# Sheet1.net
KiCad netlist of a schematic drawn in Altium Designer
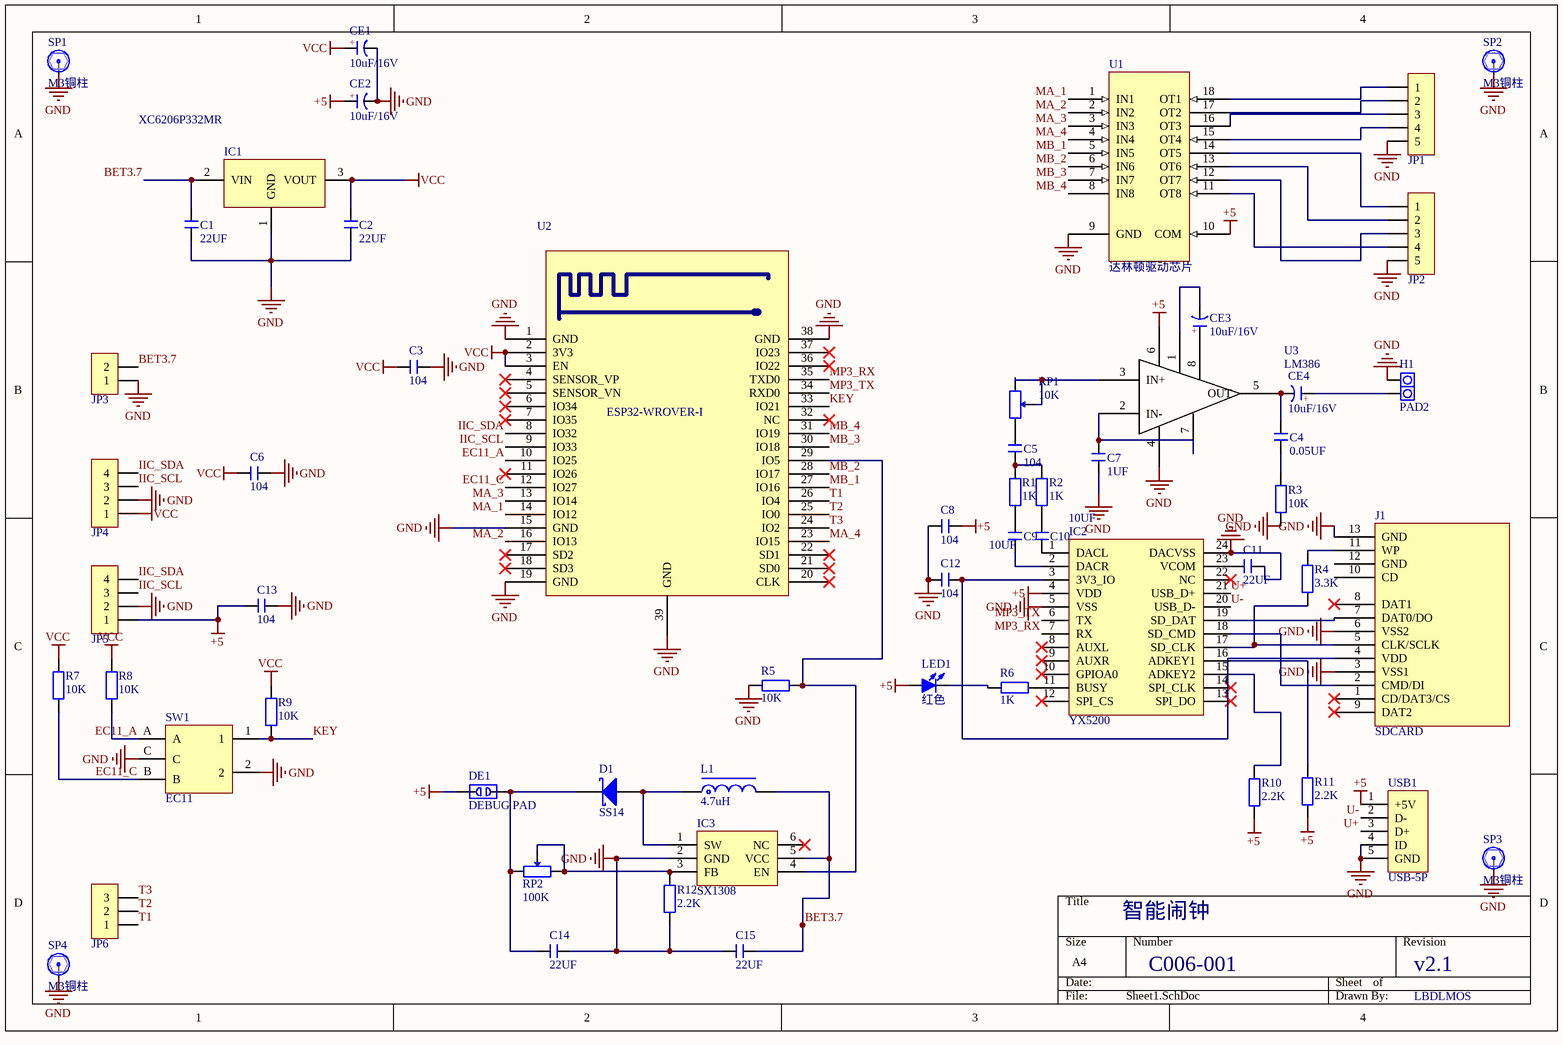
[diagram p0: Sheet1.SchDoc]

(export (version "E")
  (design (tool "Eeschema 10.0.6"))
  (components
    (comp (ref "C1")
      (value "22UF")
      (footprint "C 0603_L")
      (description "贴片电容")
      (libsource (lib "0.1 - 电阻-电容-电感") (part "C"))
    )
    (comp (ref "C2")
      (value "22UF")
      (footprint "C 0603_L")
      (description "贴片电容")
      (libsource (lib "0.1 - 电阻-电容-电感") (part "C"))
    )
    (comp (ref "C3")
      (value "104")
      (footprint "C 0805_L")
      (description "贴片电容")
      (libsource (lib "0.1 - 电阻-电容-电感") (part "C"))
    )
    (comp (ref "C4")
      (value "0.05UF")
      (footprint "C 0603_L")
      (description "贴片电容")
      (libsource (lib "0.1 - 电阻-电容-电感") (part "C"))
    )
    (comp (ref "C5")
      (value "104")
      (footprint "C 0805_L")
      (description "贴片电容")
      (libsource (lib "0.1 - 电阻-电容-电感") (part "C"))
    )
    (comp (ref "C6")
      (value "104")
      (footprint "C 0805_L")
      (description "贴片电容")
      (libsource (lib "0.1 - 电阻-电容-电感") (part "C"))
    )
    (comp (ref "C7")
      (value "1UF")
      (footprint "C 0603_L")
      (description "贴片电容")
      (libsource (lib "0.1 - 电阻-电容-电感") (part "C"))
    )
    (comp (ref "C8")
      (value "104")
      (footprint "C 0603_L")
      (description "贴片电容")
      (libsource (lib "0.1 - 电阻-电容-电感") (part "C"))
    )
    (comp (ref "C9")
      (value "10UF")
      (footprint "C 0603_L")
      (description "贴片电容")
      (libsource (lib "0.1 - 电阻-电容-电感") (part "C"))
    )
    (comp (ref "C10")
      (value "10UF")
      (footprint "C 0603_L")
      (description "贴片电容")
      (libsource (lib "0.1 - 电阻-电容-电感") (part "C"))
    )
    (comp (ref "C11")
      (value "22UF")
      (footprint "C 0805_L")
      (description "贴片电容")
      (libsource (lib "0.1 - 电阻-电容-电感") (part "C"))
    )
    (comp (ref "C12")
      (value "104")
      (footprint "C 0603_L")
      (description "贴片电容")
      (libsource (lib "0.1 - 电阻-电容-电感") (part "C"))
    )
    (comp (ref "C13")
      (value "104")
      (footprint "C 0805_L")
      (description "贴片电容")
      (libsource (lib "0.1 - 电阻-电容-电感") (part "C"))
    )
    (comp (ref "C14")
      (value "22UF")
      (footprint "C 0603_L")
      (description "贴片电容")
      (libsource (lib "0.1 - 电阻-电容-电感") (part "C"))
    )
    (comp (ref "C15")
      (value "22UF")
      (footprint "C 0603_L")
      (description "贴片电容")
      (libsource (lib "0.1 - 电阻-电容-电感") (part "C"))
    )
    (comp (ref "CE1")
      (value "10uF/16V")
      (footprint "CAP 1.5*4*8")
      (description "直插电解电容")
      (libsource (lib "0.1 - 电阻-电容-电感") (part "CE"))
    )
    (comp (ref "CE2")
      (value "10uF/16V")
      (footprint "CAP 1.5*4*8")
      (description "直插电解电容")
      (libsource (lib "0.1 - 电阻-电容-电感") (part "CE"))
    )
    (comp (ref "CE3")
      (value "10uF/16V")
      (footprint "CAP 1.5*4*8")
      (description "直插电解电容")
      (libsource (lib "") (part "CE_1"))
    )
    (comp (ref "CE4")
      (value "10uF/16V")
      (footprint "CAP 1.5*4*8")
      (description "直插电解电容")
      (libsource (lib "0.1 - 电阻-电容-电感") (part "CE"))
    )
    (comp (ref "D1")
      (value "SS14")
      (footprint "SMA")
      (description "肖特基二极管")
      (libsource (lib "0.2 -  二极管-整流桥") (part "SS14"))
    )
    (comp (ref "DE1")
      (value "DEBUG PAD")
      (footprint "DEBUG_A")
      (description "调试断点焊盘")
      (fields (field (name "版权归属") "封装库来自淘宝 ID：黄晶宝石"))
      (libsource (lib "4.1 - 未分类器件") (part "DEBUG"))
    )
    (comp (ref "H1")
      (value "PAD2")
      (footprint "PAD2-5.08")
      (description "引线焊盘")
      (fields (field (name "版权归属") "封装库来自淘宝 ID：黄晶宝石"))
      (libsource (lib "4.1 - 未分类器件") (part "PAD2"))
    )
    (comp (ref "IC1")
      (value "XC6206P332MR")
      (footprint "SOT-23")
      (libsource (lib "1.1 - 电源类芯片") (part "XC6206P332MR"))
    )
    (comp (ref "IC2")
      (value "YX5200")
      (footprint "SSOP24_N")
      (description "MP3解码芯片")
      (fields (field (name "版权归属") "封装库来自淘宝 ID：黄晶宝石"))
      (libsource (lib "1.0 - 常见芯片") (part "YX5200"))
    )
    (comp (ref "IC3")
      (value "SX1308")
      (footprint "SOT23-6N")
      (description "可调升压芯片")
      (fields (field (name "版权归属") "封装库来自淘宝 ID：黄晶宝石"))
      (libsource (lib "1.1 - 电源类芯片") (part "SX1308"))
    )
    (comp (ref "J1")
      (value "SDCARD")
      (footprint "SDCARD_B")
      (description "SD卡自弹")
      (libsource (lib "1.0 - 常见芯片") (part "SDCARD"))
    )
    (comp (ref "JP1")
      (value "HDR-1X5")
      (footprint "HDR2.54-LI-5P")
      (description "5P接插件")
      (fields (field (name "版权归属") "封装库来自淘宝 ID：黄晶宝石"))
      (libsource (lib "5.3 - 接插件-脚距2.54 (100mil) ") (part "Header 5"))
    )
    (comp (ref "JP2")
      (value "HDR-1X5")
      (footprint "HDR2.54-LI-5P")
      (description "5P接插件")
      (fields (field (name "版权归属") "封装库来自淘宝 ID：黄晶宝石"))
      (libsource (lib "5.3 - 接插件-脚距2.54 (100mil) ") (part "Header 5"))
    )
    (comp (ref "JP3")
      (value "HDR-1X2")
      (footprint "HDR2.54-LI-2P")
      (description "2P接插件")
      (fields (field (name "版权归属") "封装库来自淘宝 ID：黄晶宝石"))
      (libsource (lib "5.3 - 接插件-脚距2.54 (100mil) ") (part "Header 2"))
    )
    (comp (ref "JP4")
      (value "HDR-1X4")
      (footprint "XH2.54-WI-4P")
      (description "4P接插件")
      (fields (field (name "版权归属") "封装库来自淘宝 ID：黄晶宝石"))
      (libsource (lib "5.3 - 接插件-脚距2.54 (100mil) ") (part "Header 4"))
    )
    (comp (ref "JP5")
      (value "HDR-1X4")
      (footprint "XH2.54-WI-4P")
      (description "4P接插件")
      (fields (field (name "版权归属") "封装库来自淘宝 ID：黄晶宝石"))
      (libsource (lib "5.3 - 接插件-脚距2.54 (100mil) ") (part "Header 4"))
    )
    (comp (ref "JP6")
      (value "HDR-1X3")
      (footprint "XH2.54-WI-3P")
      (description "3P接插件")
      (fields (field (name "版权归属") "封装库来自淘宝 ID：黄晶宝石"))
      (libsource (lib "5.3 - 接插件-脚距2.54 (100mil) ") (part "Header 3"))
    )
    (comp (ref "L1")
      (value "4.7uH")
      (footprint "CDRH73")
      (description "功率屏蔽电感")
      (fields (field (name "版权归属") "封装库来自淘宝 ID：黄晶宝石"))
      (libsource (lib "0.1 - 电阻-电容-电感") (part "L-CDRH"))
    )
    (comp (ref "LED1")
      (value "红色")
      (footprint "LED 0603B")
      (description "贴片LED")
      (fields (field (name "版权归属") "封装库来自淘宝 ID：黄晶宝石"))
      (libsource (lib "0.3 - LED发光二极管") (part "LED-SMD"))
    )
    (comp (ref "R1")
      (value "1K")
      (footprint "R 0603_L")
      (description "贴片电阻")
      (fields (field (name "版权归属") "来自淘宝 ID：黄晶宝石"))
      (libsource (lib "0.1 - 电阻-电容-电感") (part "R"))
    )
    (comp (ref "R2")
      (value "1K")
      (footprint "R 0603_L")
      (description "贴片电阻")
      (fields (field (name "版权归属") "来自淘宝 ID：黄晶宝石"))
      (libsource (lib "0.1 - 电阻-电容-电感") (part "R"))
    )
    (comp (ref "R3")
      (value "10K")
      (footprint "R 0603_L")
      (description "贴片电阻")
      (fields (field (name "版权归属") "来自淘宝 ID：黄晶宝石"))
      (libsource (lib "0.1 - 电阻-电容-电感") (part "R"))
    )
    (comp (ref "R4")
      (value "3.3K")
      (footprint "R 0603_L")
      (description "贴片电阻")
      (fields (field (name "版权归属") "来自淘宝 ID：黄晶宝石"))
      (libsource (lib "0.1 - 电阻-电容-电感") (part "R"))
    )
    (comp (ref "R5")
      (value "10K")
      (footprint "R 0805_L")
      (description "贴片电阻")
      (fields (field (name "版权归属") "来自淘宝 ID：黄晶宝石"))
      (libsource (lib "0.1 - 电阻-电容-电感") (part "R"))
    )
    (comp (ref "R6")
      (value "1K")
      (footprint "R 0603_L")
      (description "贴片电阻")
      (fields (field (name "版权归属") "来自淘宝 ID：黄晶宝石"))
      (libsource (lib "0.1 - 电阻-电容-电感") (part "R"))
    )
    (comp (ref "R7")
      (value "10K")
      (footprint "R 0603_L")
      (description "贴片电阻")
      (fields (field (name "版权归属") "来自淘宝 ID：黄晶宝石"))
      (libsource (lib "0.1 - 电阻-电容-电感") (part "R"))
    )
    (comp (ref "R8")
      (value "10K")
      (footprint "R 0603_L")
      (description "贴片电阻")
      (fields (field (name "版权归属") "来自淘宝 ID：黄晶宝石"))
      (libsource (lib "0.1 - 电阻-电容-电感") (part "R"))
    )
    (comp (ref "R9")
      (value "10K")
      (footprint "R 0603_L")
      (description "贴片电阻")
      (fields (field (name "版权归属") "来自淘宝 ID：黄晶宝石"))
      (libsource (lib "0.1 - 电阻-电容-电感") (part "R"))
    )
    (comp (ref "R10")
      (value "2.2K")
      (footprint "R 0603_L")
      (description "贴片电阻")
      (fields (field (name "版权归属") "来自淘宝 ID：黄晶宝石"))
      (libsource (lib "0.1 - 电阻-电容-电感") (part "R"))
    )
    (comp (ref "R11")
      (value "2.2K")
      (footprint "R 0603_L")
      (description "贴片电阻")
      (fields (field (name "版权归属") "来自淘宝 ID：黄晶宝石"))
      (libsource (lib "0.1 - 电阻-电容-电感") (part "R"))
    )
    (comp (ref "R12")
      (value "2.2K")
      (footprint "R 0603_L")
      (description "贴片电阻")
      (fields (field (name "版权归属") "来自淘宝 ID：黄晶宝石"))
      (libsource (lib "0.1 - 电阻-电容-电感") (part "R"))
    )
    (comp (ref "RP1")
      (value "10K")
      (footprint "3296W")
      (description "单联电位器")
      (fields (field (name "版权归属") "封装库来自淘宝 ID：黄晶宝石"))
      (libsource (lib "0.1 - 电阻-电容-电感") (part "RP"))
    )
    (comp (ref "RP2")
      (value "100K")
      (footprint "3296W")
      (description "单联电位器")
      (fields (field (name "版权归属") "封装库来自淘宝 ID：黄晶宝石"))
      (libsource (lib "0.1 - 电阻-电容-电感") (part "RP"))
    )
    (comp (ref "SP1")
      (value "M3铜柱")
      (footprint "M3x4+6_L")
      (description "铜柱")
      (fields (field (name "版权归属") "封装库来自淘宝 ID：黄晶宝石"))
      (libsource (lib "4.1 - 未分类器件") (part "铜柱加头小焊盘"))
    )
    (comp (ref "SP2")
      (value "M3铜柱")
      (footprint "M3x4+6_L")
      (description "铜柱")
      (fields (field (name "版权归属") "封装库来自淘宝 ID：黄晶宝石"))
      (libsource (lib "4.1 - 未分类器件") (part "铜柱加头小焊盘"))
    )
    (comp (ref "SP3")
      (value "M3铜柱")
      (footprint "M3x4+6_L")
      (description "铜柱")
      (fields (field (name "版权归属") "封装库来自淘宝 ID：黄晶宝石"))
      (libsource (lib "4.1 - 未分类器件") (part "铜柱加头小焊盘"))
    )
    (comp (ref "SP4")
      (value "M3铜柱")
      (footprint "M3x4+6_L")
      (description "铜柱")
      (fields (field (name "版权归属") "封装库来自淘宝 ID：黄晶宝石"))
      (libsource (lib "4.1 - 未分类器件") (part "铜柱加头小焊盘"))
    )
    (comp (ref "SW1")
      (value "EC11")
      (footprint "EC11-B")
      (description "数字开关编码器")
      (fields (field (name "版权归属") "封装库来自淘宝 ID：黄晶宝石"))
      (libsource (lib "0.7 - 常用按键-开关") (part "EC11"))
    )
    (comp (ref "U1")
      (value "达林顿驱动芯片")
      (footprint "DIP18-300")
      (libsource (lib "1.0 - 常见芯片") (part "ULN2803"))
    )
    (comp (ref "U2")
      (value "ESP32-WROVER-I")
      (footprint "ESP32-WROVER-I")
      (libsource (lib "0.9 - 电路模块") (part "ESP32-WROVER-I"))
    )
    (comp (ref "U3")
      (value "LM386")
      (footprint "DIP-8")
      (description "音频放大器")
      (libsource (lib "1.0 - 常见芯片") (part "LM386"))
    )
    (comp (ref "USB1")
      (value "USB-5P")
      (footprint "USB-MICRO_A")
      (description "微型USB母座")
      (libsource (lib "0.8 - 以太网-音频-USB插座") (part "USB-5P"))
    )
  )
  (nets
    (net (code "1") (name "+5") (class "Default")
      (node (ref "C13") (pin "1") (pinfunction "1_1") (pintype "passive"))
      (node (ref "C8") (pin "2") (pinfunction "2_2") (pintype "passive"))
      (node (ref "CE2") (pin "1") (pinfunction "A_1") (pintype "passive"))
      (node (ref "DE1") (pin "1") (pinfunction "1_1") (pintype "passive"))
      (node (ref "IC2") (pin "4") (pinfunction "VDD_4") (pintype "passive"))
      (node (ref "JP5") (pin "1") (pinfunction "1_1") (pintype "passive"))
      (node (ref "LED1") (pin "1") (pinfunction "A_1") (pintype "passive"))
      (node (ref "R10") (pin "1") (pinfunction "1_1") (pintype "passive"))
      (node (ref "R11") (pin "1") (pinfunction "1_1") (pintype "passive"))
      (node (ref "U1") (pin "10") (pinfunction "COM_10") (pintype "input"))
      (node (ref "U3") (pin "6") (pintype "passive"))
      (node (ref "USB1") (pin "1") (pinfunction "+5V_1") (pintype "passive"))
    )
    (net (code "2") (name "/BET3.7") (class "Default")
      (node (ref "C1") (pin "2") (pinfunction "2_2") (pintype "passive"))
      (node (ref "C15") (pin "2") (pinfunction "2_2") (pintype "passive"))
      (node (ref "IC1") (pin "2") (pinfunction "VIN_2") (pintype "passive"))
      (node (ref "IC3") (pin "5") (pinfunction "VCC_5") (pintype "passive"))
      (node (ref "JP3") (pin "2") (pinfunction "2_2") (pintype "passive"))
      (node (ref "L1") (pin "2") (pinfunction "2_2") (pintype "passive"))
    )
    (net (code "3") (name "/EC11_A") (class "Default")
      (node (ref "R8") (pin "1") (pinfunction "1_1") (pintype "passive"))
      (node (ref "SW1") (pin "A") (pinfunction "A_A") (pintype "passive"))
      (node (ref "U2") (pin "10") (pinfunction "IO25_10") (pintype "passive"))
    )
    (net (code "4") (name "/EC11_C") (class "Default")
      (node (ref "R7") (pin "1") (pinfunction "1_1") (pintype "passive"))
      (node (ref "SW1") (pin "B") (pinfunction "B_B") (pintype "passive"))
      (node (ref "U2") (pin "12") (pinfunction "IO27_12") (pintype "passive"))
    )
    (net (code "5") (name "/IIC_SCL") (class "Default")
      (node (ref "JP4") (pin "3") (pinfunction "3_3") (pintype "passive"))
      (node (ref "JP5") (pin "3") (pinfunction "3_3") (pintype "passive"))
      (node (ref "U2") (pin "9") (pinfunction "IO33_9") (pintype "passive"))
    )
    (net (code "6") (name "/IIC_SDA") (class "Default")
      (node (ref "JP4") (pin "4") (pinfunction "4_4") (pintype "passive"))
      (node (ref "JP5") (pin "4") (pinfunction "4_4") (pintype "passive"))
      (node (ref "U2") (pin "8") (pinfunction "IO32_8") (pintype "passive"))
    )
    (net (code "7") (name "/KEY") (class "Default")
      (node (ref "R9") (pin "1") (pinfunction "1_1") (pintype "passive"))
      (node (ref "SW1") (pin "1") (pinfunction "1_1") (pintype "passive"))
      (node (ref "U2") (pin "33") (pinfunction "IO21_33") (pintype "passive"))
    )
    (net (code "8") (name "/MA_1") (class "Default")
      (node (ref "U1") (pin "1") (pinfunction "IN1_1") (pintype "input"))
      (node (ref "U2") (pin "14") (pinfunction "IO12_14") (pintype "passive"))
    )
    (net (code "9") (name "/MA_2") (class "Default")
      (node (ref "U1") (pin "2") (pinfunction "IN2_2") (pintype "input"))
      (node (ref "U2") (pin "16") (pinfunction "IO13_16") (pintype "passive"))
    )
    (net (code "10") (name "/MA_3") (class "Default")
      (node (ref "U1") (pin "3") (pinfunction "IN3_3") (pintype "input"))
      (node (ref "U2") (pin "13") (pinfunction "IO14_13") (pintype "passive"))
    )
    (net (code "11") (name "/MA_4") (class "Default")
      (node (ref "U1") (pin "4") (pinfunction "IN4_4") (pintype "input"))
      (node (ref "U2") (pin "23") (pinfunction "IO15_23") (pintype "passive"))
    )
    (net (code "12") (name "/MB_1") (class "Default")
      (node (ref "U1") (pin "5") (pinfunction "IN5_5") (pintype "input"))
      (node (ref "U2") (pin "27") (pinfunction "IO16_27") (pintype "passive"))
    )
    (net (code "13") (name "/MB_2") (class "Default")
      (node (ref "U1") (pin "6") (pinfunction "IN6_6") (pintype "input"))
      (node (ref "U2") (pin "28") (pinfunction "IO17_28") (pintype "passive"))
    )
    (net (code "14") (name "/MB_3") (class "Default")
      (node (ref "U1") (pin "7") (pinfunction "IN7_7") (pintype "input"))
      (node (ref "U2") (pin "30") (pinfunction "IO18_30") (pintype "passive"))
    )
    (net (code "15") (name "/MB_4") (class "Default")
      (node (ref "U1") (pin "8") (pinfunction "IN8_8") (pintype "passive"))
      (node (ref "U2") (pin "31") (pinfunction "IO19_31") (pintype "passive"))
    )
    (net (code "16") (name "/MP3_RX") (class "Default")
      (node (ref "IC2") (pin "7") (pinfunction "RX_7") (pintype "passive"))
      (node (ref "U2") (pin "35") (pinfunction "TXD0_35") (pintype "passive"))
    )
    (net (code "17") (name "/MP3_TX") (class "Default")
      (node (ref "IC2") (pin "6") (pinfunction "TX_6") (pintype "passive"))
      (node (ref "U2") (pin "34") (pinfunction "RXD0_34") (pintype "passive"))
    )
    (net (code "18") (name "/T1") (class "Default")
      (node (ref "JP6") (pin "1") (pinfunction "1_1") (pintype "passive"))
      (node (ref "U2") (pin "26") (pinfunction "IO4_26") (pintype "passive"))
    )
    (net (code "19") (name "/T2") (class "Default")
      (node (ref "JP6") (pin "2") (pinfunction "2_2") (pintype "passive"))
      (node (ref "U2") (pin "25") (pinfunction "IO0_25") (pintype "passive"))
    )
    (net (code "20") (name "/T3") (class "Default")
      (node (ref "JP6") (pin "3") (pinfunction "3_3") (pintype "passive"))
      (node (ref "U2") (pin "24") (pinfunction "IO2_24") (pintype "passive"))
    )
    (net (code "21") (name "/U+") (class "Default")
      (node (ref "IC2") (pin "21") (pinfunction "USB_D+_21") (pintype "passive"))
      (node (ref "USB1") (pin "3") (pinfunction "D+_3") (pintype "passive"))
    )
    (net (code "22") (name "/U-") (class "Default")
      (node (ref "IC2") (pin "20") (pinfunction "USB_D-_20") (pintype "passive"))
      (node (ref "USB1") (pin "2") (pinfunction "D-_2") (pintype "passive"))
    )
    (net (code "23") (name "GND") (class "Default")
      (node (ref "C1") (pin "1") (pinfunction "1_1") (pintype "passive"))
      (node (ref "C11") (pin "2") (pinfunction "2_2") (pintype "passive"))
      (node (ref "C12") (pin "1") (pinfunction "1_1") (pintype "passive"))
      (node (ref "C13") (pin "2") (pinfunction "2_2") (pintype "passive"))
      (node (ref "C14") (pin "2") (pinfunction "2_2") (pintype "passive"))
      (node (ref "C15") (pin "1") (pinfunction "1_1") (pintype "passive"))
      (node (ref "C2") (pin "1") (pinfunction "1_1") (pintype "passive"))
      (node (ref "C3") (pin "2") (pinfunction "2_2") (pintype "passive"))
      (node (ref "C6") (pin "2") (pinfunction "2_2") (pintype "passive"))
      (node (ref "C7") (pin "1") (pinfunction "1_1") (pintype "passive"))
      (node (ref "C8") (pin "1") (pinfunction "1_1") (pintype "passive"))
      (node (ref "CE1") (pin "2") (pinfunction "K_2") (pintype "passive"))
      (node (ref "CE2") (pin "2") (pinfunction "K_2") (pintype "passive"))
      (node (ref "H1") (pin "1") (pinfunction "1_1") (pintype "passive"))
      (node (ref "IC1") (pin "1") (pinfunction "GND_1") (pintype "passive"))
      (node (ref "IC2") (pin "24") (pinfunction "DACVSS_24") (pintype "passive"))
      (node (ref "IC2") (pin "5") (pinfunction "VSS_5") (pintype "passive"))
      (node (ref "IC3") (pin "2") (pinfunction "GND_2") (pintype "passive"))
      (node (ref "J1") (pin "13") (pinfunction "GND_13") (pintype "passive"))
      (node (ref "J1") (pin "3") (pinfunction "VSS1_3") (pintype "passive"))
      (node (ref "J1") (pin "6") (pinfunction "VSS2_6") (pintype "passive"))
      (node (ref "JP1") (pin "5") (pinfunction "5_5") (pintype "passive"))
      (node (ref "JP2") (pin "5") (pinfunction "5_5") (pintype "passive"))
      (node (ref "JP3") (pin "1") (pinfunction "1_1") (pintype "passive"))
      (node (ref "JP4") (pin "2") (pinfunction "2_2") (pintype "passive"))
      (node (ref "JP5") (pin "2") (pinfunction "2_2") (pintype "passive"))
      (node (ref "R12") (pin "1") (pinfunction "1_1") (pintype "passive"))
      (node (ref "R3") (pin "1") (pinfunction "1_1") (pintype "passive"))
      (node (ref "R5") (pin "1") (pinfunction "1_1") (pintype "passive"))
      (node (ref "SP1") (pin "1") (pinfunction "1_1") (pintype "passive"))
      (node (ref "SP2") (pin "1") (pinfunction "1_1") (pintype "passive"))
      (node (ref "SP3") (pin "1") (pinfunction "1_1") (pintype "passive"))
      (node (ref "SP4") (pin "1") (pinfunction "1_1") (pintype "passive"))
      (node (ref "SW1") (pin "2") (pinfunction "2_2") (pintype "passive"))
      (node (ref "SW1") (pin "C") (pinfunction "C_C") (pintype "passive"))
      (node (ref "U1") (pin "9") (pinfunction "GND_9") (pintype "power_in"))
      (node (ref "U2") (pin "1") (pinfunction "GND_1") (pintype "passive"))
      (node (ref "U2") (pin "15") (pinfunction "GND_15") (pintype "passive"))
      (node (ref "U2") (pin "19") (pinfunction "GND_19") (pintype "passive"))
      (node (ref "U2") (pin "38") (pinfunction "GND_38") (pintype "passive"))
      (node (ref "U2") (pin "39") (pinfunction "GND_39") (pintype "passive"))
      (node (ref "U3") (pin "4") (pintype "passive"))
      (node (ref "USB1") (pin "4") (pinfunction "ID_4") (pintype "passive"))
      (node (ref "USB1") (pin "5") (pinfunction "GND_5") (pintype "passive"))
    )
    (net (code "24") (name "Net-(C4-Pad1)") (class "Default")
      (node (ref "C4") (pin "1") (pinfunction "1_1") (pintype "passive"))
      (node (ref "R3") (pin "2") (pinfunction "2_2") (pintype "passive"))
    )
    (net (code "25") (name "Net-(C5-Pad1)") (class "Default")
      (node (ref "C5") (pin "1") (pinfunction "1_1") (pintype "passive"))
      (node (ref "R1") (pin "2") (pinfunction "2_2") (pintype "passive"))
      (node (ref "R2") (pin "2") (pinfunction "2_2") (pintype "passive"))
    )
    (net (code "26") (name "Net-(C5-Pad2)") (class "Default")
      (node (ref "C5") (pin "2") (pinfunction "2_2") (pintype "passive"))
      (node (ref "RP1") (pin "3") (pinfunction "3_3") (pintype "passive"))
    )
    (net (code "27") (name "Net-(C9-Pad2)") (class "Default")
      (node (ref "C9") (pin "2") (pinfunction "2_2") (pintype "passive"))
      (node (ref "R1") (pin "1") (pinfunction "1_1") (pintype "passive"))
    )
    (net (code "28") (name "Net-(C10-Pad2)") (class "Default")
      (node (ref "C10") (pin "2") (pinfunction "2_2") (pintype "passive"))
      (node (ref "R2") (pin "1") (pinfunction "1_1") (pintype "passive"))
    )
    (net (code "29") (name "Net-(CE3-A)") (class "Default")
      (node (ref "CE3") (pin "1") (pinfunction "A_1") (pintype "passive"))
      (node (ref "U3") (pin "8") (pintype "passive"))
    )
    (net (code "30") (name "Net-(CE3-K)") (class "Default")
      (node (ref "CE3") (pin "2") (pinfunction "K_2") (pintype "passive"))
      (node (ref "U3") (pin "1") (pintype "passive"))
    )
    (net (code "31") (name "Net-(CE4-A)") (class "Default")
      (node (ref "CE4") (pin "1") (pinfunction "A_1") (pintype "passive"))
      (node (ref "H1") (pin "2") (pinfunction "2_2") (pintype "passive"))
    )
    (net (code "32") (name "Net-(CE4-K)") (class "Default")
      (node (ref "C4") (pin "2") (pinfunction "2_2") (pintype "passive"))
      (node (ref "CE4") (pin "2") (pinfunction "K_2") (pintype "passive"))
      (node (ref "U3") (pin "5") (pinfunction "OUT_5") (pintype "passive"))
    )
    (net (code "33") (name "Net-(D1-A)") (class "Default")
      (node (ref "D1") (pin "1") (pinfunction "A_1") (pintype "passive"))
      (node (ref "IC3") (pin "1") (pinfunction "SW_1") (pintype "passive"))
      (node (ref "L1") (pin "1") (pinfunction "1_1") (pintype "passive"))
    )
    (net (code "34") (name "Net-(D1-K)") (class "Default")
      (node (ref "C14") (pin "1") (pinfunction "1_1") (pintype "passive"))
      (node (ref "D1") (pin "2") (pinfunction "K_2") (pintype "passive"))
      (node (ref "DE1") (pin "2") (pinfunction "2_2") (pintype "passive"))
      (node (ref "RP2") (pin "1") (pinfunction "1_1") (pintype "passive"))
    )
    (net (code "35") (name "Net-(IC2-3V3_IO)") (class "Default")
      (node (ref "C12") (pin "2") (pinfunction "2_2") (pintype "passive"))
      (node (ref "IC2") (pin "3") (pinfunction "3V3_IO_3") (pintype "passive"))
      (node (ref "J1") (pin "4") (pinfunction "VDD_4") (pintype "passive"))
    )
    (net (code "36") (name "Net-(IC2-ADKEY1)") (class "Default")
      (node (ref "IC2") (pin "16") (pinfunction "ADKEY1_16") (pintype "passive"))
      (node (ref "R11") (pin "2") (pinfunction "2_2") (pintype "passive"))
    )
    (net (code "37") (name "Net-(IC2-ADKEY2)") (class "Default")
      (node (ref "IC2") (pin "15") (pinfunction "ADKEY2_15") (pintype "passive"))
      (node (ref "R10") (pin "2") (pinfunction "2_2") (pintype "passive"))
    )
    (net (code "38") (name "Net-(IC2-BUSY)") (class "Default")
      (node (ref "IC2") (pin "11") (pinfunction "BUSY_11") (pintype "passive"))
      (node (ref "R6") (pin "2") (pinfunction "2_2") (pintype "passive"))
    )
    (net (code "39") (name "Net-(IC2-DACL)") (class "Default")
      (node (ref "C10") (pin "1") (pinfunction "1_1") (pintype "passive"))
      (node (ref "IC2") (pin "1") (pinfunction "DACL_1") (pintype "passive"))
    )
    (net (code "40") (name "Net-(IC2-DACR)") (class "Default")
      (node (ref "C9") (pin "1") (pinfunction "1_1") (pintype "passive"))
      (node (ref "IC2") (pin "2") (pinfunction "DACR_2") (pintype "passive"))
    )
    (net (code "41") (name "Net-(IC2-SD_CLK)") (class "Default")
      (node (ref "IC2") (pin "17") (pinfunction "SD_CLK_17") (pintype "passive"))
      (node (ref "J1") (pin "5") (pinfunction "CLK/SCLK_5") (pintype "passive"))
      (node (ref "R4") (pin "1") (pinfunction "1_1") (pintype "passive"))
    )
    (net (code "42") (name "Net-(IC2-SD_CMD)") (class "Default")
      (node (ref "IC2") (pin "18") (pinfunction "SD_CMD_18") (pintype "passive"))
      (node (ref "J1") (pin "2") (pinfunction "CMD/DI_2") (pintype "passive"))
    )
    (net (code "43") (name "Net-(IC2-SD_DAT)") (class "Default")
      (node (ref "IC2") (pin "19") (pinfunction "SD_DAT_19") (pintype "passive"))
      (node (ref "J1") (pin "7") (pinfunction "DAT0/DO_7") (pintype "passive"))
    )
    (net (code "44") (name "Net-(IC2-VCOM)") (class "Default")
      (node (ref "C11") (pin "1") (pinfunction "1_1") (pintype "passive"))
      (node (ref "IC2") (pin "23") (pinfunction "VCOM_23") (pintype "passive"))
    )
    (net (code "45") (name "Net-(IC3-EN)") (class "Default")
      (node (ref "IC3") (pin "4") (pinfunction "EN_4") (pintype "passive"))
      (node (ref "R5") (pin "2") (pinfunction "2_2") (pintype "passive"))
      (node (ref "U2") (pin "29") (pinfunction "IO5_29") (pintype "passive"))
    )
    (net (code "46") (name "Net-(IC3-FB)") (class "Default")
      (node (ref "IC3") (pin "3") (pinfunction "FB_3") (pintype "passive"))
      (node (ref "R12") (pin "2") (pinfunction "2_2") (pintype "passive"))
      (node (ref "RP2") (pin "2") (pinfunction "2_2") (pintype "passive"))
      (node (ref "RP2") (pin "3") (pinfunction "3_3") (pintype "passive"))
    )
    (net (code "47") (name "Net-(J1-WP)") (class "Default")
      (node (ref "J1") (pin "11") (pinfunction "WP_11") (pintype "passive"))
      (node (ref "R4") (pin "2") (pinfunction "2_2") (pintype "passive"))
    )
    (net (code "48") (name "Net-(LED1-K)") (class "Default")
      (node (ref "LED1") (pin "2") (pinfunction "K_2") (pintype "passive"))
      (node (ref "R6") (pin "1") (pinfunction "1_1") (pintype "passive"))
    )
    (net (code "49") (name "Net-(U1-OT1)") (class "Default")
      (node (ref "JP1") (pin "1") (pinfunction "1_1") (pintype "passive"))
      (node (ref "U1") (pin "18") (pinfunction "OT1_18") (pintype "input"))
    )
    (net (code "50") (name "Net-(U1-OT2)") (class "Default")
      (node (ref "JP1") (pin "2") (pinfunction "2_2") (pintype "passive"))
      (node (ref "U1") (pin "17") (pinfunction "OT2_17") (pintype "passive"))
    )
    (net (code "51") (name "Net-(U1-OT3)") (class "Default")
      (node (ref "JP1") (pin "3") (pinfunction "3_3") (pintype "passive"))
      (node (ref "U1") (pin "16") (pinfunction "OT3_16") (pintype "power_in"))
    )
    (net (code "52") (name "Net-(U1-OT4)") (class "Default")
      (node (ref "JP1") (pin "4") (pinfunction "4_4") (pintype "passive"))
      (node (ref "U1") (pin "15") (pinfunction "OT4_15") (pintype "input"))
    )
    (net (code "53") (name "Net-(U1-OT5)") (class "Default")
      (node (ref "JP2") (pin "1") (pinfunction "1_1") (pintype "passive"))
      (node (ref "U1") (pin "14") (pinfunction "OT5_14") (pintype "tri_state"))
    )
    (net (code "54") (name "Net-(U1-OT6)") (class "Default")
      (node (ref "JP2") (pin "2") (pinfunction "2_2") (pintype "passive"))
      (node (ref "U1") (pin "13") (pinfunction "OT6_13") (pintype "input"))
    )
    (net (code "55") (name "Net-(U1-OT7)") (class "Default")
      (node (ref "JP2") (pin "3") (pinfunction "3_3") (pintype "passive"))
      (node (ref "U1") (pin "12") (pinfunction "OT7_12") (pintype "input"))
    )
    (net (code "56") (name "Net-(U1-OT8)") (class "Default")
      (node (ref "JP2") (pin "4") (pinfunction "4_4") (pintype "passive"))
      (node (ref "U1") (pin "11") (pinfunction "OT8_11") (pintype "input"))
    )
    (net (code "57") (name "Net-(U3-IN+)") (class "Default")
      (node (ref "RP1") (pin "1") (pinfunction "1_1") (pintype "passive"))
      (node (ref "RP1") (pin "2") (pinfunction "2_2") (pintype "passive"))
      (node (ref "U3") (pin "3") (pinfunction "IN+_3") (pintype "passive"))
    )
    (net (code "58") (name "Net-(U3-IN-)") (class "Default")
      (node (ref "C7") (pin "2") (pinfunction "2_2") (pintype "passive"))
      (node (ref "U3") (pin "2") (pinfunction "IN-_2") (pintype "passive"))
      (node (ref "U3") (pin "7") (pintype "passive"))
    )
    (net (code "59") (name "VCC") (class "Default")
      (node (ref "C2") (pin "2") (pinfunction "2_2") (pintype "passive"))
      (node (ref "C3") (pin "1") (pinfunction "1_1") (pintype "passive"))
      (node (ref "C6") (pin "1") (pinfunction "1_1") (pintype "passive"))
      (node (ref "CE1") (pin "1") (pinfunction "A_1") (pintype "passive"))
      (node (ref "IC1") (pin "3") (pinfunction "VOUT_3") (pintype "passive"))
      (node (ref "JP4") (pin "1") (pinfunction "1_1") (pintype "passive"))
      (node (ref "R7") (pin "2") (pinfunction "2_2") (pintype "passive"))
      (node (ref "R8") (pin "2") (pinfunction "2_2") (pintype "passive"))
      (node (ref "R9") (pin "2") (pinfunction "2_2") (pintype "passive"))
      (node (ref "U2") (pin "2") (pinfunction "3V3_2") (pintype "passive"))
      (node (ref "U2") (pin "3") (pinfunction "EN_3") (pintype "passive"))
    )
    (net (code "60") (name "unconnected-(IC2-AUXL-Pad8)") (class "Default")
      (node (ref "IC2") (pin "8") (pinfunction "AUXL_8") (pintype "passive+no_connect"))
    )
    (net (code "61") (name "unconnected-(IC2-AUXR-Pad9)") (class "Default")
      (node (ref "IC2") (pin "9") (pinfunction "AUXR_9") (pintype "passive+no_connect"))
    )
    (net (code "62") (name "unconnected-(IC2-GPIOA0-Pad10)") (class "Default")
      (node (ref "IC2") (pin "10") (pinfunction "GPIOA0_10") (pintype "passive+no_connect"))
    )
    (net (code "63") (name "unconnected-(IC2-NC-Pad22)") (class "Default")
      (node (ref "IC2") (pin "22") (pinfunction "NC_22") (pintype "passive+no_connect"))
    )
    (net (code "64") (name "unconnected-(IC2-SPI_CLK-Pad14)") (class "Default")
      (node (ref "IC2") (pin "14") (pinfunction "SPI_CLK_14") (pintype "passive+no_connect"))
    )
    (net (code "65") (name "unconnected-(IC2-SPI_CS-Pad12)") (class "Default")
      (node (ref "IC2") (pin "12") (pinfunction "SPI_CS_12") (pintype "passive+no_connect"))
    )
    (net (code "66") (name "unconnected-(IC2-SPI_DO-Pad13)") (class "Default")
      (node (ref "IC2") (pin "13") (pinfunction "SPI_DO_13") (pintype "passive+no_connect"))
    )
    (net (code "67") (name "unconnected-(IC3-NC-Pad6)") (class "Default")
      (node (ref "IC3") (pin "6") (pinfunction "NC_6") (pintype "passive+no_connect"))
    )
    (net (code "68") (name "unconnected-(J1-CD-Pad10)") (class "Default")
      (node (ref "J1") (pin "10") (pinfunction "CD_10") (pintype "passive"))
    )
    (net (code "69") (name "unconnected-(J1-CD{slash}DAT3{slash}CS-Pad1)") (class "Default")
      (node (ref "J1") (pin "1") (pinfunction "CD/DAT3/CS_1") (pintype "passive+no_connect"))
    )
    (net (code "70") (name "unconnected-(J1-DAT1-Pad8)") (class "Default")
      (node (ref "J1") (pin "8") (pinfunction "DAT1_8") (pintype "passive+no_connect"))
    )
    (net (code "71") (name "unconnected-(J1-DAT2-Pad9)") (class "Default")
      (node (ref "J1") (pin "9") (pinfunction "DAT2_9") (pintype "passive+no_connect"))
    )
    (net (code "72") (name "unconnected-(J1-GND-Pad12)") (class "Default")
      (node (ref "J1") (pin "12") (pinfunction "GND_12") (pintype "passive"))
    )
    (net (code "73") (name "unconnected-(U2-CLK-Pad20)") (class "Default")
      (node (ref "U2") (pin "20") (pinfunction "CLK_20") (pintype "passive+no_connect"))
    )
    (net (code "74") (name "unconnected-(U2-IO22-Pad36)") (class "Default")
      (node (ref "U2") (pin "36") (pinfunction "IO22_36") (pintype "passive+no_connect"))
    )
    (net (code "75") (name "unconnected-(U2-IO23-Pad37)") (class "Default")
      (node (ref "U2") (pin "37") (pinfunction "IO23_37") (pintype "passive+no_connect"))
    )
    (net (code "76") (name "unconnected-(U2-IO26-Pad11)") (class "Default")
      (node (ref "U2") (pin "11") (pinfunction "IO26_11") (pintype "passive+no_connect"))
    )
    (net (code "77") (name "unconnected-(U2-IO34-Pad6)") (class "Default")
      (node (ref "U2") (pin "6") (pinfunction "IO34_6") (pintype "passive+no_connect"))
    )
    (net (code "78") (name "unconnected-(U2-IO35-Pad7)") (class "Default")
      (node (ref "U2") (pin "7") (pinfunction "IO35_7") (pintype "passive+no_connect"))
    )
    (net (code "79") (name "unconnected-(U2-NC-Pad32)") (class "Default")
      (node (ref "U2") (pin "32") (pinfunction "NC_32") (pintype "passive+no_connect"))
    )
    (net (code "80") (name "unconnected-(U2-SD0-Pad21)") (class "Default")
      (node (ref "U2") (pin "21") (pinfunction "SD0_21") (pintype "passive+no_connect"))
    )
    (net (code "81") (name "unconnected-(U2-SD1-Pad22)") (class "Default")
      (node (ref "U2") (pin "22") (pinfunction "SD1_22") (pintype "passive+no_connect"))
    )
    (net (code "82") (name "unconnected-(U2-SD2-Pad17)") (class "Default")
      (node (ref "U2") (pin "17") (pinfunction "SD2_17") (pintype "passive+no_connect"))
    )
    (net (code "83") (name "unconnected-(U2-SD3-Pad18)") (class "Default")
      (node (ref "U2") (pin "18") (pinfunction "SD3_18") (pintype "passive+no_connect"))
    )
    (net (code "84") (name "unconnected-(U2-SENSOR_VN-Pad5)") (class "Default")
      (node (ref "U2") (pin "5") (pinfunction "SENSOR_VN_5") (pintype "passive+no_connect"))
    )
    (net (code "85") (name "unconnected-(U2-SENSOR_VP-Pad4)") (class "Default")
      (node (ref "U2") (pin "4") (pinfunction "SENSOR_VP_4") (pintype "passive+no_connect"))
    )
  )
)
